# Peripherals.net
KiCad netlist of a schematic drawn in Altium Designer
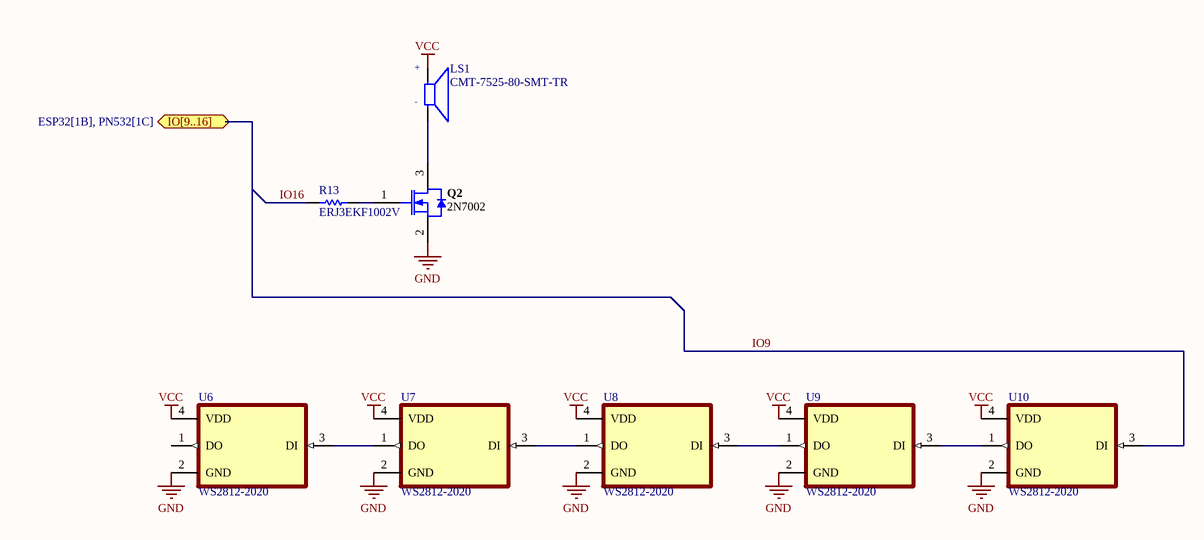
[diagram p0: Peripherals.SchDoc]

(export (version "E")
  (design (tool "Eeschema 10.0.6"))
  (components
    (comp (ref "LS1")
      (value "CMT-7525-80-SMT-TR")
      (footprint "CMT-7525-80-SMT-TR:XDCR_CMT-7525-80-SMT-TR")
      (fields (field (name "MF") "{'manufacturer': u'CUI Devices'}"))
      (libsource (lib "*") (part "CMT-7525-80-SMT-TR"))
    )
    (comp (ref "Q2")
      (value "2N7002")
      (footprint "INF-PG-SOT23_M")
      (fields (field (name "MANUFACTURER") "Infineon"))
      (libsource (lib "Altium Content Vault") (part "INF-NDMOS-GSD-3"))
    )
    (comp (ref "R13")
      (value "ERJ3EKF1002V")
      (footprint "RESC1609X55X30LL15T15")
      (description "Chip Resistor, 10 KOhm, +/- 1%, 0.1 W, -55 to 155 degC, 0603 (1608 Metric), RoHS, Tape and Reel")
      (fields (field (name "TOLERANCE") "1%") (field (name "MANUFACTURER") "Panasonic"))
      (libsource (lib "Altium Content Vault") (part "RES-2"))
    )
    (comp (ref "U6")
      (value "WS2812-2020")
      (footprint "WS2812-2020:LED_WS2812-2020")
      (fields (field (name "MF") "{'manufacturer': u'Worldsemi'}"))
      (libsource (lib "*") (part "WS2812-2020"))
    )
    (comp (ref "U7")
      (value "WS2812-2020")
      (footprint "WS2812-2020:LED_WS2812-2020")
      (fields (field (name "MF") "{'manufacturer': u'Worldsemi'}"))
      (libsource (lib "*") (part "WS2812-2020"))
    )
    (comp (ref "U8")
      (value "WS2812-2020")
      (footprint "WS2812-2020:LED_WS2812-2020")
      (fields (field (name "MF") "{'manufacturer': u'Worldsemi'}"))
      (libsource (lib "*") (part "WS2812-2020"))
    )
    (comp (ref "U9")
      (value "WS2812-2020")
      (footprint "WS2812-2020:LED_WS2812-2020")
      (fields (field (name "MF") "{'manufacturer': u'Worldsemi'}"))
      (libsource (lib "*") (part "WS2812-2020"))
    )
    (comp (ref "U10")
      (value "WS2812-2020")
      (footprint "WS2812-2020:LED_WS2812-2020")
      (fields (field (name "MF") "{'manufacturer': u'Worldsemi'}"))
      (libsource (lib "*") (part "WS2812-2020"))
    )
  )
  (nets
    (net (code "7") (name "/IO9") (class "Default")
      (node (ref "U10") (pin "3") (pinfunction "DI_3") (pintype "input"))
    )
    (net (code "8") (name "/IO16") (class "Default")
      (node (ref "R13") (pin "1") (pinfunction "1_1") (pintype "passive"))
    )
    (net (code "10") (name "GND") (class "Default")
      (node (ref "Q2") (pin "2") (pinfunction "SOURCE_2") (pintype "passive"))
      (node (ref "U10") (pin "2") (pinfunction "GND_2") (pintype "power_in"))
      (node (ref "U6") (pin "2") (pinfunction "GND_2") (pintype "power_in"))
      (node (ref "U7") (pin "2") (pinfunction "GND_2") (pintype "power_in"))
      (node (ref "U8") (pin "2") (pinfunction "GND_2") (pintype "power_in"))
      (node (ref "U9") (pin "2") (pinfunction "GND_2") (pintype "power_in"))
    )
    (net (code "11") (name "Net-(Q2-DRAIN)") (class "Default")
      (node (ref "LS1") (pin "N") (pinfunction "N_N") (pintype "passive"))
      (node (ref "Q2") (pin "3") (pinfunction "DRAIN_3") (pintype "passive"))
    )
    (net (code "12") (name "Net-(Q2-GATE)") (class "Default")
      (node (ref "Q2") (pin "1") (pinfunction "GATE_1") (pintype "passive"))
      (node (ref "R13") (pin "2") (pinfunction "2_2") (pintype "passive"))
    )
    (net (code "13") (name "Net-(U6-DI)") (class "Default")
      (node (ref "U6") (pin "3") (pinfunction "DI_3") (pintype "input"))
      (node (ref "U7") (pin "1") (pinfunction "DO_1") (pintype "output"))
    )
    (net (code "14") (name "Net-(U7-DI)") (class "Default")
      (node (ref "U7") (pin "3") (pinfunction "DI_3") (pintype "input"))
      (node (ref "U8") (pin "1") (pinfunction "DO_1") (pintype "output"))
    )
    (net (code "15") (name "Net-(U8-DI)") (class "Default")
      (node (ref "U8") (pin "3") (pinfunction "DI_3") (pintype "input"))
      (node (ref "U9") (pin "1") (pinfunction "DO_1") (pintype "output"))
    )
    (net (code "16") (name "Net-(U10-DO)") (class "Default")
      (node (ref "U10") (pin "1") (pinfunction "DO_1") (pintype "output"))
      (node (ref "U9") (pin "3") (pinfunction "DI_3") (pintype "input"))
    )
    (net (code "17") (name "VCC") (class "Default")
      (node (ref "LS1") (pin "P") (pinfunction "P_P") (pintype "passive"))
      (node (ref "U10") (pin "4") (pinfunction "VDD_4") (pintype "power_in"))
      (node (ref "U6") (pin "4") (pinfunction "VDD_4") (pintype "power_in"))
      (node (ref "U7") (pin "4") (pinfunction "VDD_4") (pintype "power_in"))
      (node (ref "U8") (pin "4") (pinfunction "VDD_4") (pintype "power_in"))
      (node (ref "U9") (pin "4") (pinfunction "VDD_4") (pintype "power_in"))
    )
    (net (code "18") (name "unconnected-(U6-DO-Pad1)") (class "Default")
      (node (ref "U6") (pin "1") (pinfunction "DO_1") (pintype "output"))
    )
  )
)
